# I2C_Multiplexer.net
KiCad netlist of a schematic drawn in Altium Designer
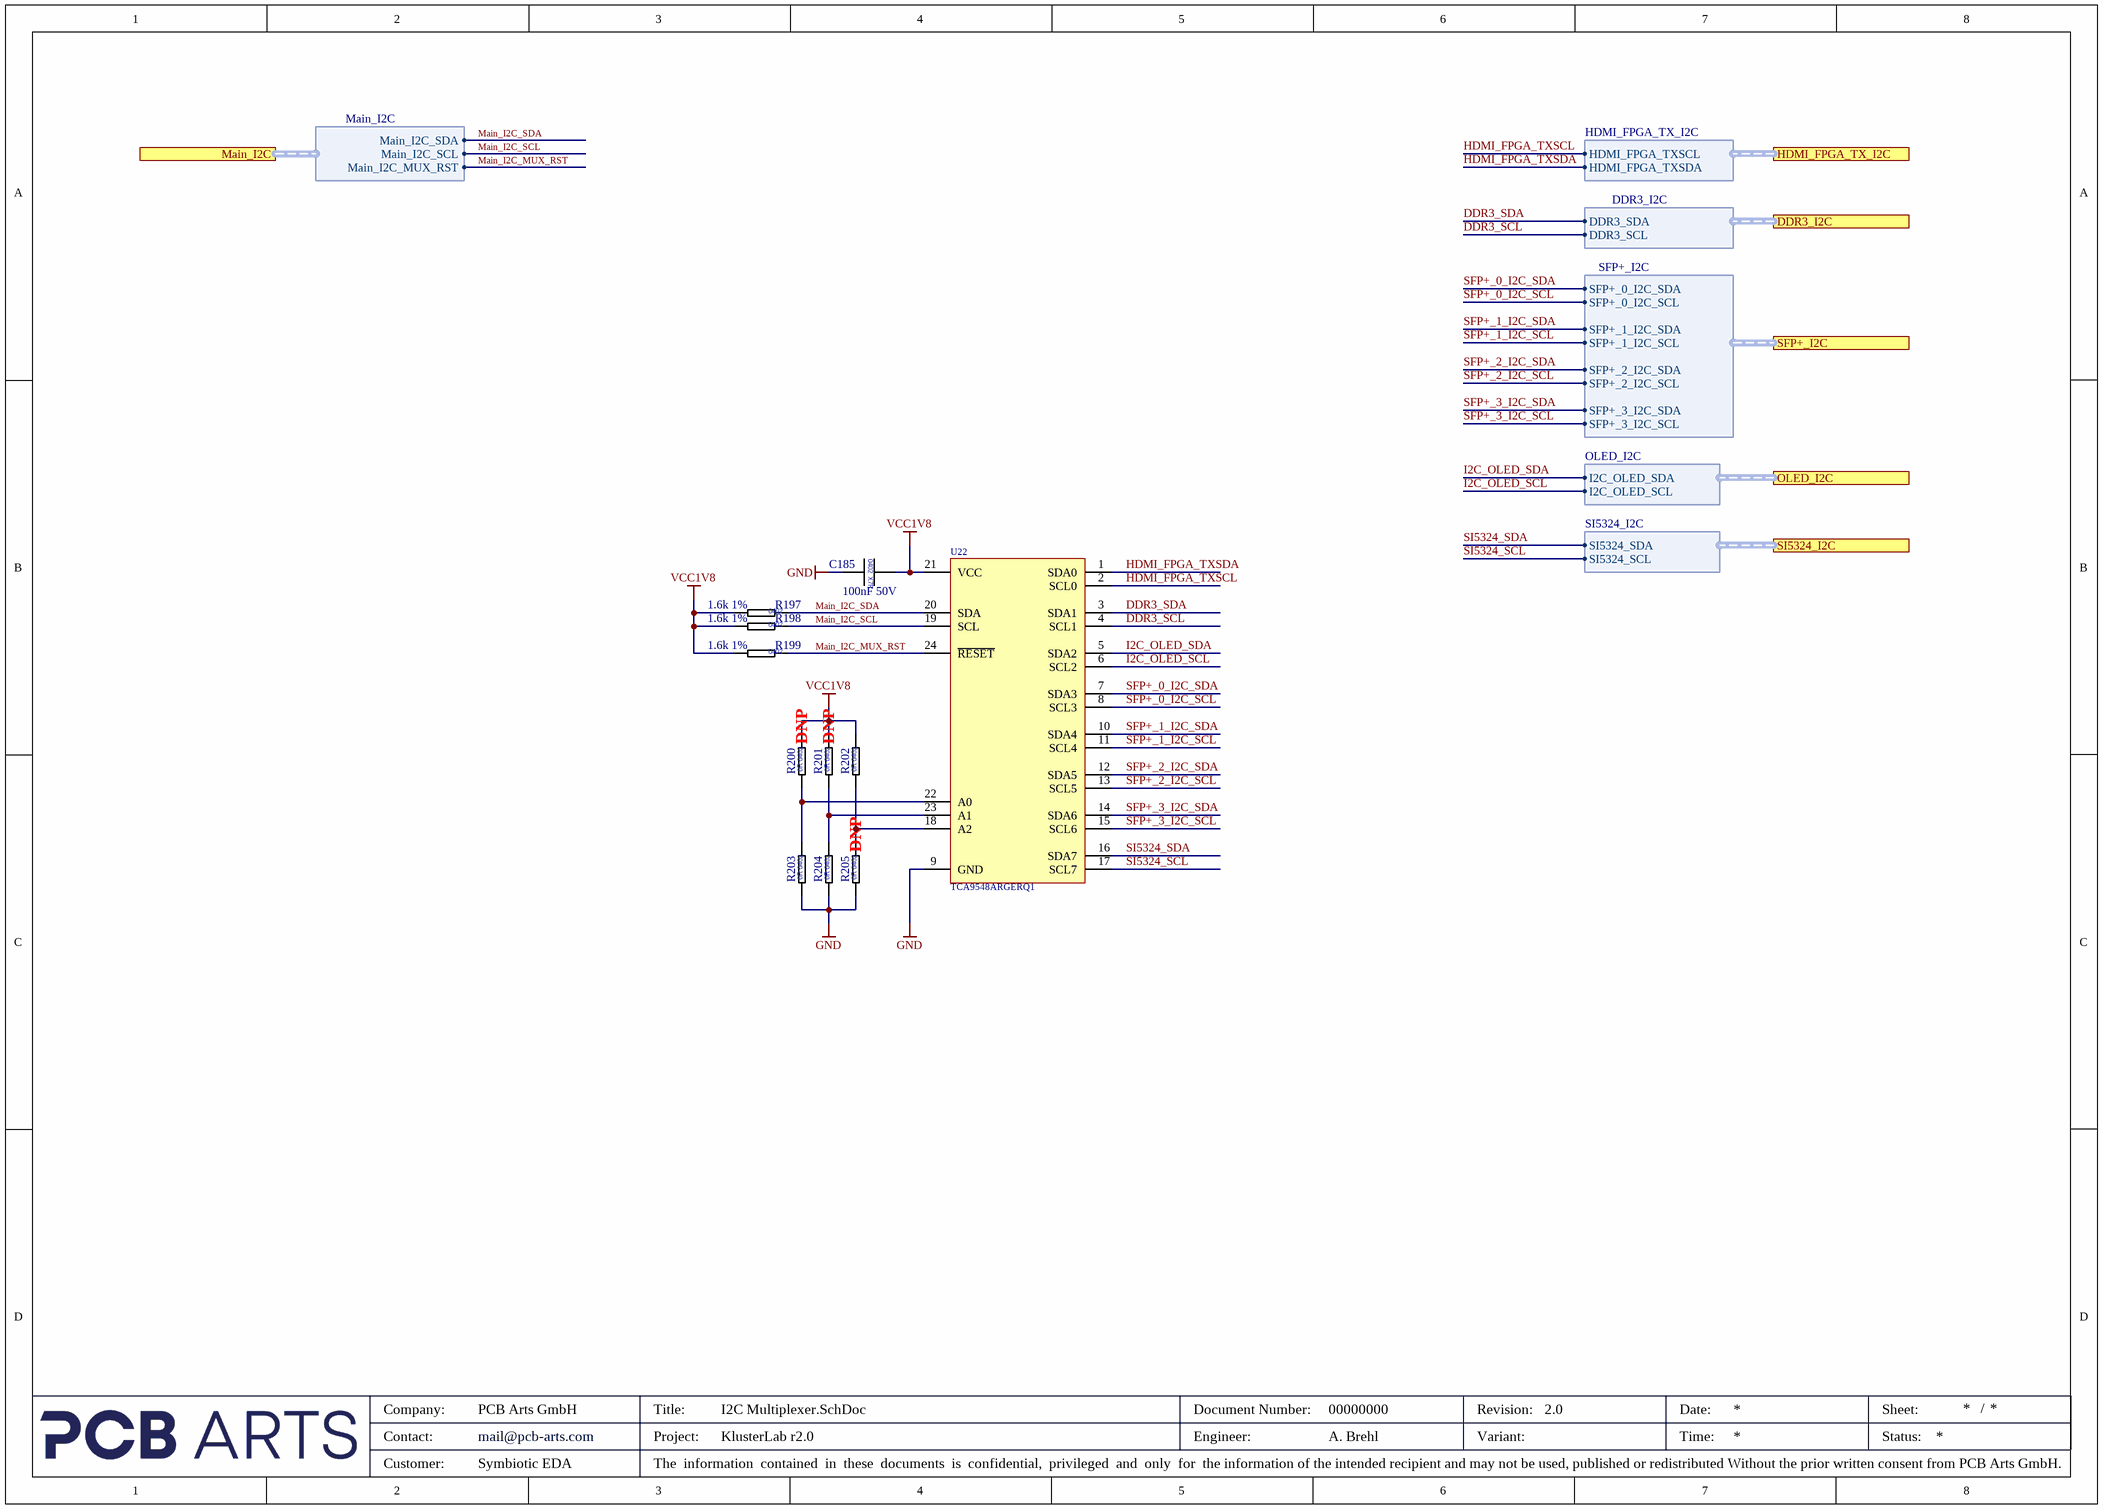
[diagram p0: I2C Multiplexer.SchDoc]

(export (version "E")
  (design (tool "Eeschema 10.0.6"))
  (components
    (comp (ref "C185")
      (value "100nF 50V")
      (footprint "Cap:CAP_0402_L")
      (description "Multilayer Ceramic Capacitors MLCC - SMD/SMT 0402 50VDC")
      (libsource (lib "Cap") (part "CAP_0402_100nF_50V"))
    )
    (comp (ref "R197")
      (value "1.6k 1%")
      (footprint "Res:RES_0402_L")
      (description "Thick Film Resistors - SMD 1.6kOhm 1%")
      (libsource (lib "Res") (part "RES_0402_1.6k_1%"))
    )
    (comp (ref "R198")
      (value "1.6k 1%")
      (footprint "Res:RES_0402_L")
      (description "Thick Film Resistors - SMD 1.6kOhm 1%")
      (libsource (lib "Res") (part "RES_0402_1.6k_1%"))
    )
    (comp (ref "R199")
      (value "1.6k 1%")
      (footprint "Res:RES_0402_L")
      (description "Thick Film Resistors - SMD 1.6kOhm 1%")
      (libsource (lib "Res") (part "RES_0402_1.6k_1%"))
    )
    (comp (ref "R200")
      (value "0R Jumper")
      (footprint "Res:RES_0402_L")
      (description "Thick Film Resistors - SMD 0Ohm")
      (libsource (lib "Res") (part "RES_0402_0R Jumper"))
    )
    (comp (ref "R201")
      (value "0R Jumper")
      (footprint "Res:RES_0402_L")
      (description "Thick Film Resistors - SMD 0Ohm")
      (libsource (lib "Res") (part "RES_0402_0R Jumper"))
    )
    (comp (ref "R202")
      (value "0R Jumper")
      (footprint "Res:RES_0402_L")
      (description "Thick Film Resistors - SMD 0Ohm")
      (libsource (lib "Res") (part "RES_0402_0R Jumper"))
    )
    (comp (ref "R203")
      (value "0R Jumper")
      (footprint "Res:RES_0402_L")
      (description "Thick Film Resistors - SMD 0Ohm")
      (libsource (lib "Res") (part "RES_0402_0R Jumper"))
    )
    (comp (ref "R204")
      (value "0R Jumper")
      (footprint "Res:RES_0402_L")
      (description "Thick Film Resistors - SMD 0Ohm")
      (libsource (lib "Res") (part "RES_0402_0R Jumper"))
    )
    (comp (ref "R205")
      (value "0R Jumper")
      (footprint "Res:RES_0402_L")
      (description "Thick Film Resistors - SMD 0Ohm")
      (libsource (lib "Res") (part "RES_0402_0R Jumper"))
    )
    (comp (ref "U22")
      (value "TCA9548ARGERQ1")
      (footprint "digital:QFN50P400X400X100-25N")
      (description "Automotive 8-Channel I2C Switch with Reset")
      (libsource (lib "Digital") (part "TCA9548ARGERQ1_8-Channel I2C Switch with Reset"))
    )
  )
  (nets
    (net (code "7") (name "/DDR3_SCL") (class "Default")
      (node (ref "U22") (pin "4") (pinfunction "SCL1_4") (pintype "passive"))
    )
    (net (code "8") (name "/DDR3_SDA") (class "Default")
      (node (ref "U22") (pin "3") (pinfunction "SDA1_3") (pintype "passive"))
    )
    (net (code "9") (name "/HDMI_FPGA_TXSCL") (class "Default")
      (node (ref "U22") (pin "2") (pinfunction "SCL0_2") (pintype "passive"))
    )
    (net (code "10") (name "/HDMI_FPGA_TXSDA") (class "Default")
      (node (ref "U22") (pin "1") (pinfunction "SDA0_1") (pintype "passive"))
    )
    (net (code "11") (name "/I2C_OLED_SCL") (class "Default")
      (node (ref "U22") (pin "6") (pinfunction "SCL2_6") (pintype "passive"))
    )
    (net (code "12") (name "/I2C_OLED_SDA") (class "Default")
      (node (ref "U22") (pin "5") (pinfunction "SDA2_5") (pintype "passive"))
    )
    (net (code "13") (name "/Main_I2C_MUX_RST") (class "Default")
      (node (ref "R199") (pin "1") (pinfunction "1_1") (pintype "passive"))
      (node (ref "U22") (pin "24") (pinfunction "~{RESET}_24") (pintype "passive"))
    )
    (net (code "14") (name "/Main_I2C_SCL") (class "Default")
      (node (ref "R198") (pin "1") (pinfunction "1_1") (pintype "passive"))
      (node (ref "U22") (pin "19") (pinfunction "SCL_19") (pintype "passive"))
    )
    (net (code "15") (name "/Main_I2C_SDA") (class "Default")
      (node (ref "R197") (pin "1") (pinfunction "1_1") (pintype "passive"))
      (node (ref "U22") (pin "20") (pinfunction "SDA_20") (pintype "passive"))
    )
    (net (code "16") (name "/SFP+_0_I2C_SCL") (class "Default")
      (node (ref "U22") (pin "8") (pinfunction "SCL3_8") (pintype "passive"))
    )
    (net (code "17") (name "/SFP+_0_I2C_SDA") (class "Default")
      (node (ref "U22") (pin "7") (pinfunction "SDA3_7") (pintype "passive"))
    )
    (net (code "18") (name "/SFP+_1_I2C_SCL") (class "Default")
      (node (ref "U22") (pin "11") (pinfunction "SCL4_11") (pintype "passive"))
    )
    (net (code "19") (name "/SFP+_1_I2C_SDA") (class "Default")
      (node (ref "U22") (pin "10") (pinfunction "SDA4_10") (pintype "passive"))
    )
    (net (code "20") (name "/SFP+_2_I2C_SCL") (class "Default")
      (node (ref "U22") (pin "13") (pinfunction "SCL5_13") (pintype "passive"))
    )
    (net (code "21") (name "/SFP+_2_I2C_SDA") (class "Default")
      (node (ref "U22") (pin "12") (pinfunction "SDA5_12") (pintype "passive"))
    )
    (net (code "22") (name "/SFP+_3_I2C_SCL") (class "Default")
      (node (ref "U22") (pin "15") (pinfunction "SCL6_15") (pintype "passive"))
    )
    (net (code "23") (name "/SFP+_3_I2C_SDA") (class "Default")
      (node (ref "U22") (pin "14") (pinfunction "SDA6_14") (pintype "passive"))
    )
    (net (code "24") (name "/SI5324_SCL") (class "Default")
      (node (ref "U22") (pin "17") (pinfunction "SCL7_17") (pintype "passive"))
    )
    (net (code "25") (name "/SI5324_SDA") (class "Default")
      (node (ref "U22") (pin "16") (pinfunction "SDA7_16") (pintype "passive"))
    )
    (net (code "32") (name "GND") (class "Default")
      (node (ref "C185") (pin "2") (pinfunction "2_2") (pintype "passive"))
      (node (ref "R203") (pin "1") (pinfunction "1_1") (pintype "passive"))
      (node (ref "R204") (pin "1") (pinfunction "1_1") (pintype "passive"))
      (node (ref "R205") (pin "1") (pinfunction "1_1") (pintype "passive"))
      (node (ref "U22") (pin "9") (pinfunction "GND_9") (pintype "passive"))
    )
    (net (code "33") (name "Net-(U22-A0)") (class "Default")
      (node (ref "R200") (pin "1") (pinfunction "1_1") (pintype "passive"))
      (node (ref "R203") (pin "2") (pinfunction "2_2") (pintype "passive"))
      (node (ref "U22") (pin "22") (pinfunction "A0_22") (pintype "passive"))
    )
    (net (code "34") (name "Net-(U22-A1)") (class "Default")
      (node (ref "R201") (pin "1") (pinfunction "1_1") (pintype "passive"))
      (node (ref "R204") (pin "2") (pinfunction "2_2") (pintype "passive"))
      (node (ref "U22") (pin "23") (pinfunction "A1_23") (pintype "passive"))
    )
    (net (code "35") (name "Net-(U22-A2)") (class "Default")
      (node (ref "R202") (pin "1") (pinfunction "1_1") (pintype "passive"))
      (node (ref "R205") (pin "2") (pinfunction "2_2") (pintype "passive"))
      (node (ref "U22") (pin "18") (pinfunction "A2_18") (pintype "passive"))
    )
    (net (code "36") (name "VCC1V8") (class "Default")
      (node (ref "C185") (pin "1") (pinfunction "1_1") (pintype "passive"))
      (node (ref "R197") (pin "2") (pinfunction "2_2") (pintype "passive"))
      (node (ref "R198") (pin "2") (pinfunction "2_2") (pintype "passive"))
      (node (ref "R199") (pin "2") (pinfunction "2_2") (pintype "passive"))
      (node (ref "R200") (pin "2") (pinfunction "2_2") (pintype "passive"))
      (node (ref "R201") (pin "2") (pinfunction "2_2") (pintype "passive"))
      (node (ref "R202") (pin "2") (pinfunction "2_2") (pintype "passive"))
      (node (ref "U22") (pin "21") (pinfunction "VCC_21") (pintype "passive"))
    )
  )
)
